# CATS-FAT-Storage.net
KiCad netlist of a schematic drawn in Altium Designer
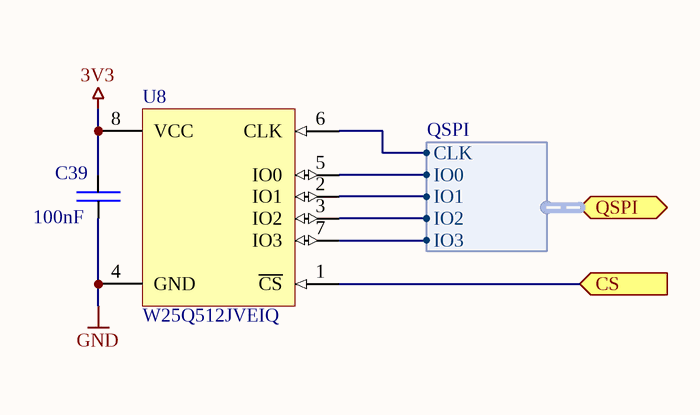
[diagram p0: CATS-FAT-Storage.SchDoc]

(export (version "E")
  (design (tool "Eeschema 10.0.6"))
  (components
    (comp (ref "C39")
      (value "100nF")
      (footprint "SMD Keramikkondensator 0603")
      (description "SMD Ceramic Capacitor E6")
      (libsource (lib "Ceramic Capacitors-E6") (part "E6 - 100nF"))
    )
    (comp (ref "U8")
      (value "W25Q512JVEIQ")
      (footprint "SMD IC WSON-8 [8x6]")
      (description "FLASH - NOR Memory IC 512Mb (64M x 8) SPI - Quad I/O 133MHz 8-WSON (8x6)")
      (libsource (lib "Digital") (part "W25Q512JVEIQ"))
    )
  )
  (nets
    (net (code "2") (name "/CLK") (class "Default")
      (node (ref "U8") (pin "6") (pinfunction "CLK_6") (pintype "input"))
    )
    (net (code "3") (name "/CS") (class "Default")
      (node (ref "U8") (pin "1") (pinfunction "~{CS}_1") (pintype "input"))
    )
    (net (code "4") (name "/IO0") (class "Default")
      (node (ref "U8") (pin "5") (pinfunction "IO0_5") (pintype "bidirectional"))
    )
    (net (code "5") (name "/IO1") (class "Default")
      (node (ref "U8") (pin "2") (pinfunction "IO1_2") (pintype "bidirectional"))
    )
    (net (code "6") (name "/IO2") (class "Default")
      (node (ref "U8") (pin "3") (pinfunction "IO2_3") (pintype "bidirectional"))
    )
    (net (code "7") (name "/IO3") (class "Default")
      (node (ref "U8") (pin "7") (pinfunction "IO3_7") (pintype "bidirectional"))
    )
    (net (code "9") (name "3V3") (class "Default")
      (node (ref "C39") (pin "2") (pinfunction "2_2") (pintype "passive"))
      (node (ref "U8") (pin "8") (pinfunction "VCC_8") (pintype "power_in"))
    )
    (net (code "10") (name "GND") (class "Default")
      (node (ref "C39") (pin "1") (pinfunction "1_1") (pintype "passive"))
      (node (ref "U8") (pin "4") (pinfunction "GND_4") (pintype "power_in"))
    )
  )
)
